# schematic-for-manuf.net
KiCad netlist of a schematic drawn in EAGLE
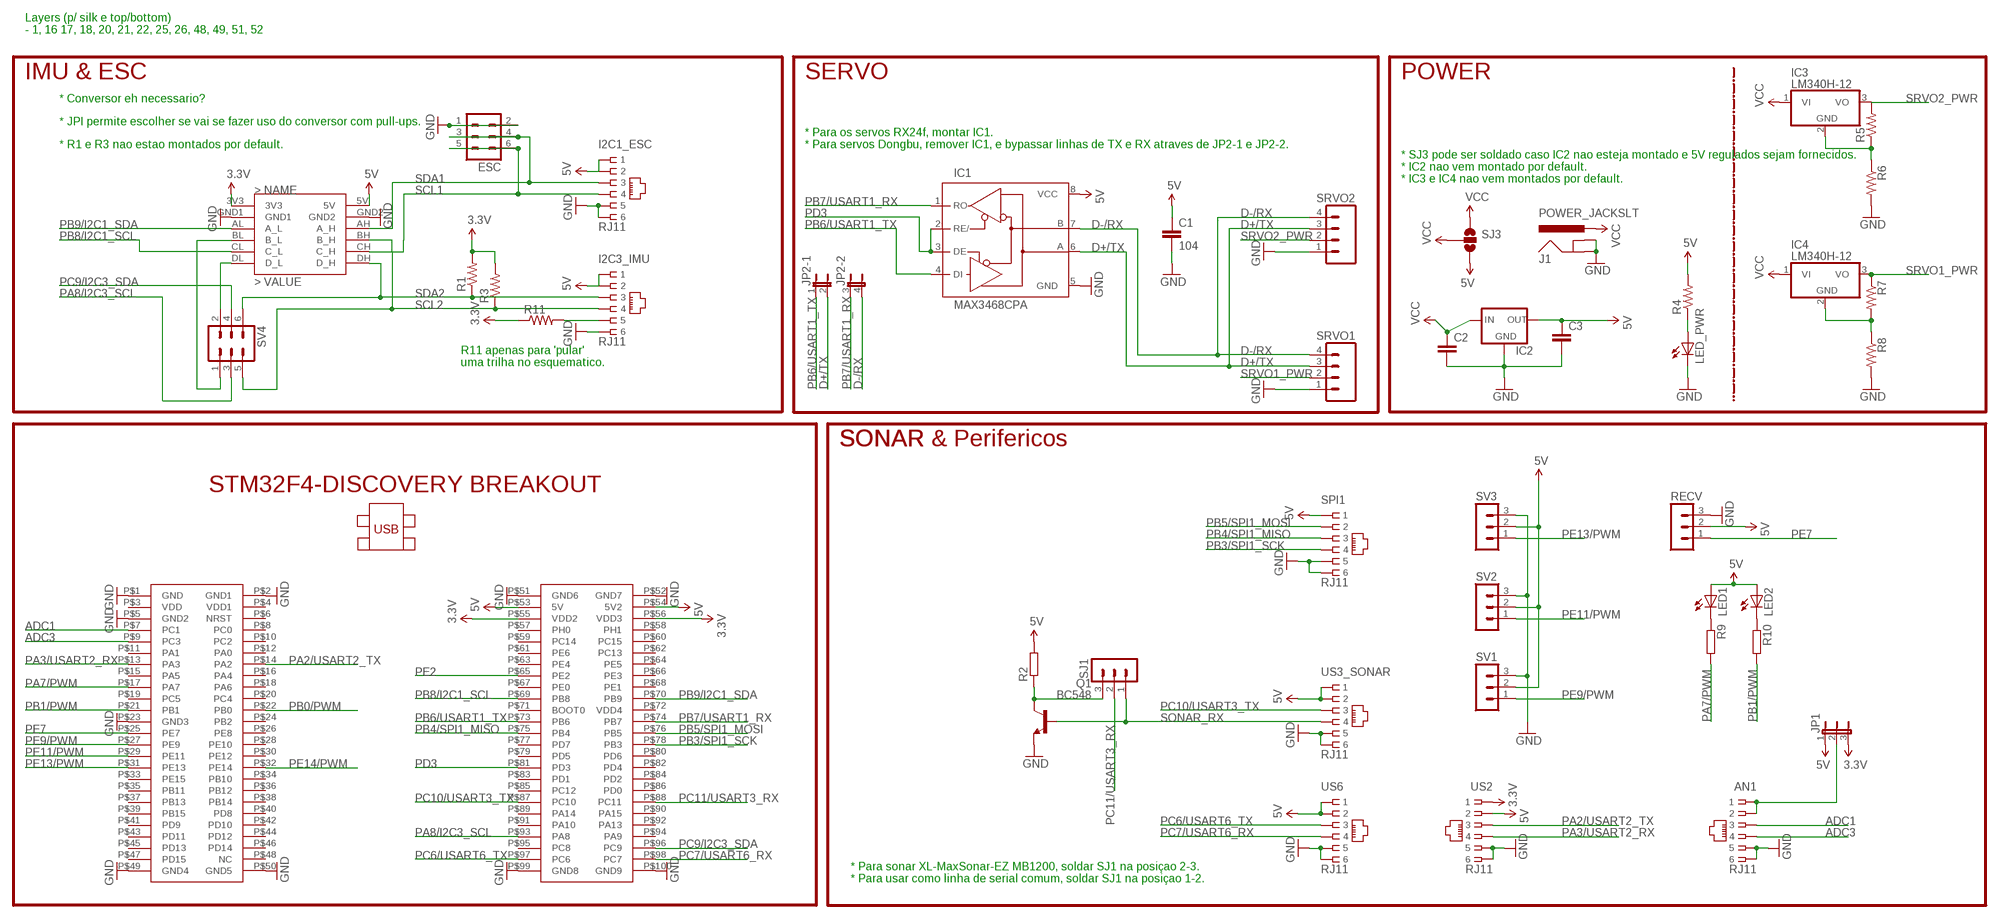
[diagram p0: schematic, sheet 1]

(export (version "E")
  (design (tool "Eeschema 10.0.6"))
  (components
    (comp (ref "AN1")
      (value "RJ11")
      (footprint "eagle-import:RJ12-PROVANT")
      (libsource (lib "eagle-import") (part "RJ11"))
    )
    (comp (ref "C1")
      (value "104")
      (footprint "eagle-import:CAP-PTH-SMALL-KIT")
      (libsource (lib "eagle-import") (part "0.1UF-50V-20%(PTH)KIT-EZ"))
    )
    (comp (ref "C2")
      (value "C7.5/3")
      (footprint "eagle-import:C7.5B3")
      (libsource (lib "eagle-import") (part "C7.5/3"))
    )
    (comp (ref "C3")
      (value "0.1UF-50V-20%(PTH)KIT-EZ")
      (footprint "eagle-import:CAP-PTH-SMALL-KIT")
      (libsource (lib "eagle-import") (part "0.1UF-50V-20%(PTH)KIT-EZ"))
    )
    (comp (ref "ESC")
      (value "MA03-2")
      (footprint "eagle-import:MA03-2")
      (libsource (lib "eagle-import") (part "MA03-2"))
    )
    (comp (ref "I2C1_ESC")
      (value "RJ11")
      (footprint "eagle-import:RJ12-PROVANT")
      (libsource (lib "eagle-import") (part "RJ11"))
    )
    (comp (ref "I2C3_IMU")
      (value "RJ11")
      (footprint "eagle-import:RJ12-PROVANT")
      (libsource (lib "eagle-import") (part "RJ11"))
    )
    (comp (ref "IC1")
      (value "MAX3468CPA")
      (footprint "eagle-import:DIL08")
      (libsource (lib "eagle-import") (part "MAX34PA68C"))
    )
    (comp (ref "IC2")
      (value "V_REG_78XX-TO-220")
      (footprint "eagle-import:TO-220-ALT")
      (libsource (lib "eagle-import") (part "V_REG_78XX-TO-220"))
    )
    (comp (ref "IC3")
      (value "LM340H-12")
      (footprint "eagle-import:TO220H")
      (libsource (lib "eagle-import") (part "LM340?-H12"))
    )
    (comp (ref "IC4")
      (value "LM340H-12")
      (footprint "eagle-import:TO220H")
      (libsource (lib "eagle-import") (part "LM340?-H12"))
    )
    (comp (ref "J1")
      (value "POWER_JACKSLT")
      (footprint "eagle-import:POWER_JACK_SLOT")
      (libsource (lib "eagle-import") (part "POWER_JACKSLT"))
    )
    (comp (ref "JP1")
      (value "JP2E")
      (footprint "eagle-import:JP2")
      (libsource (lib "eagle-import") (part "JP2E"))
    )
    (comp (ref "JP2")
      (value "JP2QE")
      (footprint "eagle-import:JP2Q")
      (libsource (lib "eagle-import") (part "JP2QE"))
    )
    (comp (ref "LED1")
      (value "LED3MM")
      (footprint "eagle-import:LED3MM")
      (libsource (lib "eagle-import") (part "LED3MM"))
    )
    (comp (ref "LED2")
      (value "LED3MM")
      (footprint "eagle-import:LED3MM")
      (libsource (lib "eagle-import") (part "LED3MM"))
    )
    (comp (ref "LED_PWR")
      (value "LED5MM")
      (footprint "eagle-import:LED5MM")
      (libsource (lib "eagle-import") (part "LED5MM"))
    )
    (comp (ref "Q1")
      (value "BC548")
      (footprint "eagle-import:TO92-EBC")
      (libsource (lib "eagle-import") (part "BC548"))
    )
    (comp (ref "R1")
      (value "R-US_0204/5")
      (footprint "eagle-import:0204_5")
      (libsource (lib "eagle-import") (part "R-US_0204/5"))
    )
    (comp (ref "R2")
      (value "R-EU_0204/7")
      (footprint "eagle-import:0204_7")
      (libsource (lib "eagle-import") (part "R-EU_0204/7"))
    )
    (comp (ref "R3")
      (value "R-US_0204/5")
      (footprint "eagle-import:0204_5")
      (libsource (lib "eagle-import") (part "R-US_0204/5"))
    )
    (comp (ref "R4")
      (value "R-US_0204/7")
      (footprint "eagle-import:0204_7")
      (libsource (lib "eagle-import") (part "R-US_0204/7"))
    )
    (comp (ref "R5")
      (value "R-US_0204/7")
      (footprint "eagle-import:0204_7")
      (libsource (lib "eagle-import") (part "R-US_0204/7"))
    )
    (comp (ref "R6")
      (value "R-US_0204/7")
      (footprint "eagle-import:0204_7")
      (libsource (lib "eagle-import") (part "R-US_0204/7"))
    )
    (comp (ref "R7")
      (value "R-US_0204/7")
      (footprint "eagle-import:0204_7")
      (libsource (lib "eagle-import") (part "R-US_0204/7"))
    )
    (comp (ref "R8")
      (value "R-US_0204/7")
      (footprint "eagle-import:0204_7")
      (libsource (lib "eagle-import") (part "R-US_0204/7"))
    )
    (comp (ref "R9")
      (value "R-EU_0204/2V")
      (footprint "eagle-import:0204V")
      (libsource (lib "eagle-import") (part "R-EU_0204/2V"))
    )
    (comp (ref "R10")
      (value "R-EU_0204/2V")
      (footprint "eagle-import:0204V")
      (libsource (lib "eagle-import") (part "R-EU_0204/2V"))
    )
    (comp (ref "R11")
      (value "R-US_M1406")
      (footprint "eagle-import:M1406")
      (libsource (lib "eagle-import") (part "R-US_M1406"))
    )
    (comp (ref "RECV")
      (value "MA03-1")
      (footprint "eagle-import:MA03-1")
      (libsource (lib "eagle-import") (part "MA03-1"))
    )
    (comp (ref "SJ1")
      (value "MA03-1")
      (footprint "eagle-import:MA03-1")
      (libsource (lib "eagle-import") (part "MA03-1"))
    )
    (comp (ref "SJ3")
      (value "SOLDERJUMPER_2WAY-OLDW")
      (footprint "eagle-import:SJ_2W")
      (libsource (lib "eagle-import") (part "SOLDERJUMPER_2WAY-OLDW"))
    )
    (comp (ref "SPI1")
      (value "RJ11")
      (footprint "eagle-import:RJ12-PROVANT")
      (libsource (lib "eagle-import") (part "RJ11"))
    )
    (comp (ref "SRVO1")
      (value "M04POLAR")
      (footprint "eagle-import:MOLEX-1X4")
      (libsource (lib "eagle-import") (part "M04POLAR"))
    )
    (comp (ref "SRVO2")
      (value "M04POLAR")
      (footprint "eagle-import:MOLEX-1X4")
      (libsource (lib "eagle-import") (part "M04POLAR"))
    )
    (comp (ref "SV1")
      (value "MA03-1")
      (footprint "eagle-import:MA03-1")
      (libsource (lib "eagle-import") (part "MA03-1"))
    )
    (comp (ref "SV2")
      (value "MA03-1")
      (footprint "eagle-import:MA03-1")
      (libsource (lib "eagle-import") (part "MA03-1"))
    )
    (comp (ref "SV3")
      (value "MA03-1")
      (footprint "eagle-import:MA03-1")
      (libsource (lib "eagle-import") (part "MA03-1"))
    )
    (comp (ref "SV4")
      (value "MA03-2")
      (footprint "eagle-import:MA03-2")
      (libsource (lib "eagle-import") (part "MA03-2"))
    )
    (comp (ref "U$1")
      (value "STM32F4-DISCOVERY")
      (footprint "eagle-import:STM32F4-DISCOVERY")
      (libsource (lib "eagle-import") (part "STM32F4-DISCOVERY"))
    )
    (comp (ref "U$2")
      (value "JYMCU_LOGIC_LEVEL_CONVERTER")
      (footprint "eagle-import:JYMCU_LOGIC_LEVEL_SHIFTER_DIP")
      (libsource (lib "eagle-import") (part "JYMCU_LOGIC_LEVEL_CONVERTER"))
    )
    (comp (ref "US2")
      (value "RJ11")
      (footprint "eagle-import:RJ12-PROVANT")
      (libsource (lib "eagle-import") (part "RJ11"))
    )
    (comp (ref "US3_SONAR")
      (value "RJ11")
      (footprint "eagle-import:RJ12-PROVANT")
      (libsource (lib "eagle-import") (part "RJ11"))
    )
    (comp (ref "US6")
      (value "RJ11")
      (footprint "eagle-import:RJ12-PROVANT")
      (libsource (lib "eagle-import") (part "RJ11"))
    )
  )
  (nets
    (net (code "1") (name "/ADC1") (class "Default")
      (node (ref "AN1") (pin "P3") (pinfunction "3_P3") (pintype "passive"))
      (node (ref "U$1") (pin "P$7") (pinfunction "PC1_P$7") (pintype "bidirectional"))
    )
    (net (code "2") (name "/ADC3") (class "Default")
      (node (ref "AN1") (pin "P4") (pinfunction "4_P4") (pintype "passive"))
      (node (ref "U$1") (pin "P$9") (pinfunction "PC3_P$9") (pintype "bidirectional"))
    )
    (net (code "3") (name "/D+{slash}TX") (class "Default")
      (node (ref "IC1") (pin "6") (pinfunction "A_6") (pintype "passive"))
      (node (ref "JP2") (pin "2") (pinfunction "2_2") (pintype "passive"))
      (node (ref "SRVO1") (pin "3") (pinfunction "3_3") (pintype "passive"))
      (node (ref "SRVO2") (pin "3") (pinfunction "3_3") (pintype "passive"))
    )
    (net (code "4") (name "/D-{slash}RX") (class "Default")
      (node (ref "IC1") (pin "7") (pinfunction "B_7") (pintype "passive"))
      (node (ref "JP2") (pin "4") (pinfunction "2_4") (pintype "passive"))
      (node (ref "SRVO1") (pin "4") (pinfunction "4_4") (pintype "passive"))
      (node (ref "SRVO2") (pin "4") (pinfunction "4_4") (pintype "passive"))
    )
    (net (code "5") (name "/PA2{slash}USART2_TX") (class "Default")
      (node (ref "U$1") (pin "P$14") (pinfunction "PA2_P$14") (pintype "bidirectional"))
      (node (ref "US2") (pin "P3") (pinfunction "3_P3") (pintype "passive"))
    )
    (net (code "6") (name "/PA3{slash}USART2_RX") (class "Default")
      (node (ref "U$1") (pin "P$13") (pinfunction "PA3_P$13") (pintype "bidirectional"))
      (node (ref "US2") (pin "P4") (pinfunction "4_P4") (pintype "passive"))
    )
    (net (code "7") (name "/PA7{slash}PWM") (class "Default")
      (node (ref "R9") (pin "2") (pinfunction "2_2") (pintype "passive"))
      (node (ref "U$1") (pin "P$17") (pinfunction "PA7_P$17") (pintype "bidirectional"))
    )
    (net (code "8") (name "/PA8{slash}I2C3_SCL") (class "Default")
      (node (ref "SV4") (pin "3") (pinfunction "3_3") (pintype "passive"))
      (node (ref "U$1") (pin "P$93") (pinfunction "PA8_P$93") (pintype "bidirectional"))
    )
    (net (code "9") (name "/PB0{slash}PWM") (class "Default")
      (node (ref "U$1") (pin "P$22") (pinfunction "PB0_P$22") (pintype "bidirectional"))
    )
    (net (code "10") (name "/PB1{slash}PWM") (class "Default")
      (node (ref "R10") (pin "2") (pinfunction "2_2") (pintype "passive"))
      (node (ref "U$1") (pin "P$21") (pinfunction "PB1_P$21") (pintype "bidirectional"))
    )
    (net (code "11") (name "/PB3{slash}SPI1_SCK") (class "Default")
      (node (ref "SPI1") (pin "P4") (pinfunction "4_P4") (pintype "passive"))
      (node (ref "U$1") (pin "P$78") (pinfunction "PB3_P$78") (pintype "bidirectional"))
    )
    (net (code "12") (name "/PB4{slash}SPI1_MISO") (class "Default")
      (node (ref "SPI1") (pin "P3") (pinfunction "3_P3") (pintype "passive"))
      (node (ref "U$1") (pin "P$75") (pinfunction "PB4_P$75") (pintype "bidirectional"))
    )
    (net (code "13") (name "/PB5{slash}SPI1_MOSI") (class "Default")
      (node (ref "SPI1") (pin "P2") (pinfunction "2_P2") (pintype "passive"))
      (node (ref "U$1") (pin "P$76") (pinfunction "PB5_P$76") (pintype "bidirectional"))
    )
    (net (code "14") (name "/PB6{slash}USART1_TX") (class "Default")
      (node (ref "IC1") (pin "4") (pinfunction "DI_4") (pintype "input"))
      (node (ref "JP2") (pin "1") (pinfunction "1_1") (pintype "passive"))
      (node (ref "U$1") (pin "P$73") (pinfunction "PB6_P$73") (pintype "bidirectional"))
    )
    (net (code "15") (name "/PB7{slash}USART1_RX") (class "Default")
      (node (ref "IC1") (pin "1") (pinfunction "RO_1") (pintype "output"))
      (node (ref "JP2") (pin "3") (pinfunction "1_3") (pintype "passive"))
      (node (ref "U$1") (pin "P$74") (pinfunction "PB7_P$74") (pintype "bidirectional"))
    )
    (net (code "16") (name "/PB8{slash}I2C1_SCL") (class "Default")
      (node (ref "U$1") (pin "P$69") (pinfunction "PB8_P$69") (pintype "bidirectional"))
      (node (ref "U$2") (pin "CL") (pinfunction "C_L_CL") (pintype "bidirectional"))
    )
    (net (code "17") (name "/PB9{slash}I2C1_SDA") (class "Default")
      (node (ref "U$1") (pin "P$70") (pinfunction "PB9_P$70") (pintype "bidirectional"))
      (node (ref "U$2") (pin "AL") (pinfunction "A_L_AL") (pintype "bidirectional"))
    )
    (net (code "18") (name "/PC6{slash}USART6_TX") (class "Default")
      (node (ref "U$1") (pin "P$97") (pinfunction "PC6_P$97") (pintype "bidirectional"))
      (node (ref "US6") (pin "P3") (pinfunction "3_P3") (pintype "passive"))
    )
    (net (code "19") (name "/PC7{slash}USART6_RX") (class "Default")
      (node (ref "U$1") (pin "P$98") (pinfunction "PC7_P$98") (pintype "bidirectional"))
      (node (ref "US6") (pin "P4") (pinfunction "4_P4") (pintype "passive"))
    )
    (net (code "20") (name "/PC9{slash}I2C3_SDA") (class "Default")
      (node (ref "SV4") (pin "4") (pinfunction "4_4") (pintype "passive"))
      (node (ref "U$1") (pin "P$96") (pinfunction "PC9_P$96") (pintype "bidirectional"))
    )
    (net (code "21") (name "/PC10{slash}USART3_TX") (class "Default")
      (node (ref "U$1") (pin "P$87") (pinfunction "PC10_P$87") (pintype "bidirectional"))
      (node (ref "US3_SONAR") (pin "P3") (pinfunction "3_P3") (pintype "passive"))
    )
    (net (code "22") (name "/PC11{slash}USART3_RX") (class "Default")
      (node (ref "SJ1") (pin "2") (pinfunction "2_2") (pintype "passive"))
      (node (ref "U$1") (pin "P$88") (pinfunction "PC11_P$88") (pintype "bidirectional"))
    )
    (net (code "23") (name "/PD3") (class "Default")
      (node (ref "IC1") (pin "2") (pinfunction "RE/_2") (pintype "input"))
      (node (ref "IC1") (pin "3") (pinfunction "DE_3") (pintype "input"))
      (node (ref "U$1") (pin "P$81") (pinfunction "PD3_P$81") (pintype "bidirectional"))
    )
    (net (code "24") (name "/PE2") (class "Default")
      (node (ref "U$1") (pin "P$65") (pinfunction "PE2_P$65") (pintype "bidirectional"))
    )
    (net (code "25") (name "/PE7") (class "Default")
      (node (ref "RECV") (pin "1") (pinfunction "1_1") (pintype "passive"))
      (node (ref "U$1") (pin "P$25") (pinfunction "PE7_P$25") (pintype "bidirectional"))
    )
    (net (code "26") (name "/PE9{slash}PWM") (class "Default")
      (node (ref "SV1") (pin "1") (pinfunction "1_1") (pintype "passive"))
      (node (ref "U$1") (pin "P$27") (pinfunction "PE9_P$27") (pintype "bidirectional"))
    )
    (net (code "27") (name "/PE11{slash}PWM") (class "Default")
      (node (ref "SV2") (pin "1") (pinfunction "1_1") (pintype "passive"))
      (node (ref "U$1") (pin "P$29") (pinfunction "PE11_P$29") (pintype "bidirectional"))
    )
    (net (code "28") (name "/PE13{slash}PWM") (class "Default")
      (node (ref "SV3") (pin "1") (pinfunction "1_1") (pintype "passive"))
      (node (ref "U$1") (pin "P$31") (pinfunction "PE13_P$31") (pintype "bidirectional"))
    )
    (net (code "29") (name "/PE14{slash}PWM") (class "Default")
      (node (ref "U$1") (pin "P$32") (pinfunction "PE14_P$32") (pintype "bidirectional"))
    )
    (net (code "30") (name "/SCL1") (class "Default")
      (node (ref "ESC") (pin "5") (pinfunction "5_5") (pintype "passive"))
      (node (ref "ESC") (pin "6") (pinfunction "6_6") (pintype "passive"))
      (node (ref "I2C1_ESC") (pin "P4") (pinfunction "4_P4") (pintype "passive"))
      (node (ref "U$2") (pin "CH") (pinfunction "C_H_CH") (pintype "bidirectional"))
    )
    (net (code "31") (name "/SCL2") (class "Default")
      (node (ref "I2C3_IMU") (pin "P4") (pinfunction "4_P4") (pintype "passive"))
      (node (ref "R3") (pin "1") (pinfunction "1_1") (pintype "passive"))
      (node (ref "SV4") (pin "5") (pinfunction "5_5") (pintype "passive"))
      (node (ref "U$2") (pin "BH") (pinfunction "B_H_BH") (pintype "bidirectional"))
    )
    (net (code "32") (name "/SDA1") (class "Default")
      (node (ref "ESC") (pin "3") (pinfunction "3_3") (pintype "passive"))
      (node (ref "ESC") (pin "4") (pinfunction "4_4") (pintype "passive"))
      (node (ref "I2C1_ESC") (pin "P3") (pinfunction "3_P3") (pintype "passive"))
      (node (ref "U$2") (pin "AH") (pinfunction "A_H_AH") (pintype "bidirectional"))
    )
    (net (code "33") (name "/SDA2") (class "Default")
      (node (ref "I2C3_IMU") (pin "P3") (pinfunction "3_P3") (pintype "passive"))
      (node (ref "R1") (pin "1") (pinfunction "1_1") (pintype "passive"))
      (node (ref "SV4") (pin "6") (pinfunction "6_6") (pintype "passive"))
      (node (ref "U$2") (pin "DH") (pinfunction "D_H_DH") (pintype "bidirectional"))
    )
    (net (code "34") (name "/SONAR_RX") (class "Default")
      (node (ref "Q1") (pin "B") (pinfunction "B_B") (pintype "passive"))
      (node (ref "SJ1") (pin "1") (pinfunction "1_1") (pintype "passive"))
      (node (ref "US3_SONAR") (pin "P4") (pinfunction "4_P4") (pintype "passive"))
    )
    (net (code "35") (name "/SRVO1_PWR") (class "Default")
      (node (ref "IC4") (pin "3") (pinfunction "VO_3") (pintype "passive"))
      (node (ref "R7") (pin "1") (pinfunction "1_1") (pintype "passive"))
      (node (ref "SRVO1") (pin "2") (pinfunction "2_2") (pintype "passive"))
    )
    (net (code "36") (name "/SRVO2_PWR") (class "Default")
      (node (ref "IC3") (pin "3") (pinfunction "VO_3") (pintype "passive"))
      (node (ref "R5") (pin "2") (pinfunction "2_2") (pintype "passive"))
      (node (ref "SRVO2") (pin "2") (pinfunction "2_2") (pintype "passive"))
    )
    (net (code "37") (name "3.3V") (class "Default")
      (node (ref "JP1") (pin "3") (pinfunction "3_3") (pintype "passive"))
      (node (ref "R1") (pin "2") (pinfunction "2_2") (pintype "passive"))
      (node (ref "R11") (pin "1") (pinfunction "1_1") (pintype "passive"))
      (node (ref "R3") (pin "2") (pinfunction "2_2") (pintype "passive"))
      (node (ref "U$1") (pin "P$55") (pinfunction "VDD2_P$55") (pintype "bidirectional"))
      (node (ref "U$1") (pin "P$56") (pinfunction "VDD3_P$56") (pintype "bidirectional"))
      (node (ref "U$2") (pin "3V3") (pinfunction "3V3_3V3") (pintype "bidirectional"))
      (node (ref "US2") (pin "P1") (pinfunction "1_P1") (pintype "passive"))
    )
    (net (code "38") (name "5V") (class "Default")
      (node (ref "C1") (pin "1") (pinfunction "1_1") (pintype "passive"))
      (node (ref "C3") (pin "1") (pinfunction "1_1") (pintype "passive"))
      (node (ref "I2C1_ESC") (pin "P1") (pinfunction "1_P1") (pintype "passive"))
      (node (ref "I2C1_ESC") (pin "P2") (pinfunction "2_P2") (pintype "passive"))
      (node (ref "I2C3_IMU") (pin "P1") (pinfunction "1_P1") (pintype "passive"))
      (node (ref "I2C3_IMU") (pin "P2") (pinfunction "2_P2") (pintype "passive"))
      (node (ref "IC1") (pin "8") (pinfunction "VCC_8") (pintype "power_in"))
      (node (ref "IC2") (pin "OUT") (pinfunction "OUT_OUT") (pintype "output"))
      (node (ref "JP1") (pin "1") (pinfunction "1_1") (pintype "passive"))
      (node (ref "LED1") (pin "A") (pinfunction "A_A") (pintype "passive"))
      (node (ref "LED2") (pin "A") (pinfunction "A_A") (pintype "passive"))
      (node (ref "R2") (pin "2") (pinfunction "2_2") (pintype "passive"))
      (node (ref "R4") (pin "2") (pinfunction "2_2") (pintype "passive"))
      (node (ref "RECV") (pin "2") (pinfunction "2_2") (pintype "passive"))
      (node (ref "SJ3") (pin "3") (pinfunction "3_3") (pintype "passive"))
      (node (ref "SPI1") (pin "P1") (pinfunction "1_P1") (pintype "passive"))
      (node (ref "SV1") (pin "2") (pinfunction "2_2") (pintype "passive"))
      (node (ref "SV2") (pin "2") (pinfunction "2_2") (pintype "passive"))
      (node (ref "SV3") (pin "2") (pinfunction "2_2") (pintype "passive"))
      (node (ref "U$1") (pin "P$53") (pinfunction "5V_P$53") (pintype "bidirectional"))
      (node (ref "U$1") (pin "P$54") (pinfunction "5V2_P$54") (pintype "bidirectional"))
      (node (ref "U$2") (pin "5V") (pinfunction "5V_5V") (pintype "bidirectional"))
      (node (ref "US2") (pin "P2") (pinfunction "2_P2") (pintype "passive"))
      (node (ref "US3_SONAR") (pin "P1") (pinfunction "1_P1") (pintype "passive"))
      (node (ref "US3_SONAR") (pin "P2") (pinfunction "2_P2") (pintype "passive"))
      (node (ref "US6") (pin "P1") (pinfunction "1_P1") (pintype "passive"))
      (node (ref "US6") (pin "P2") (pinfunction "2_P2") (pintype "passive"))
    )
    (net (code "39") (name "GND") (class "Default")
      (node (ref "AN1") (pin "P5") (pinfunction "5_P5") (pintype "passive"))
      (node (ref "AN1") (pin "P6") (pinfunction "6_P6") (pintype "passive"))
      (node (ref "C1") (pin "2") (pinfunction "2_2") (pintype "passive"))
      (node (ref "C2") (pin "2") (pinfunction "2_2") (pintype "passive"))
      (node (ref "C3") (pin "2") (pinfunction "2_2") (pintype "passive"))
      (node (ref "ESC") (pin "1") (pinfunction "1_1") (pintype "passive"))
      (node (ref "ESC") (pin "2") (pinfunction "2_2") (pintype "passive"))
      (node (ref "I2C1_ESC") (pin "P5") (pinfunction "5_P5") (pintype "passive"))
      (node (ref "I2C1_ESC") (pin "P6") (pinfunction "6_P6") (pintype "passive"))
      (node (ref "I2C3_IMU") (pin "P6") (pinfunction "6_P6") (pintype "passive"))
      (node (ref "IC1") (pin "5") (pinfunction "GND_5") (pintype "power_in"))
      (node (ref "IC2") (pin "GND") (pinfunction "GND_GND") (pintype "input"))
      (node (ref "J1") (pin "GND@1") (pinfunction "GNDBREAK_GND@1") (pintype "bidirectional"))
      (node (ref "J1") (pin "GND@2") (pinfunction "GND_GND@2") (pintype "bidirectional"))
      (node (ref "LED_PWR") (pin "K") (pinfunction "C_K") (pintype "passive"))
      (node (ref "Q1") (pin "E") (pinfunction "E_E") (pintype "passive"))
      (node (ref "R6") (pin "2") (pinfunction "2_2") (pintype "passive"))
      (node (ref "R8") (pin "2") (pinfunction "2_2") (pintype "passive"))
      (node (ref "RECV") (pin "3") (pinfunction "3_3") (pintype "passive"))
      (node (ref "SPI1") (pin "P5") (pinfunction "5_P5") (pintype "passive"))
      (node (ref "SPI1") (pin "P6") (pinfunction "6_P6") (pintype "passive"))
      (node (ref "SRVO1") (pin "1") (pinfunction "1_1") (pintype "passive"))
      (node (ref "SRVO2") (pin "1") (pinfunction "1_1") (pintype "passive"))
      (node (ref "SV1") (pin "3") (pinfunction "3_3") (pintype "passive"))
      (node (ref "SV2") (pin "3") (pinfunction "3_3") (pintype "passive"))
      (node (ref "SV3") (pin "3") (pinfunction "3_3") (pintype "passive"))
      (node (ref "U$1") (pin "P$1") (pinfunction "GND_P$1") (pintype "bidirectional"))
      (node (ref "U$1") (pin "P$100") (pinfunction "GND9_P$100") (pintype "bidirectional"))
      (node (ref "U$1") (pin "P$2") (pinfunction "GND1_P$2") (pintype "bidirectional"))
      (node (ref "U$1") (pin "P$23") (pinfunction "GND3_P$23") (pintype "bidirectional"))
      (node (ref "U$1") (pin "P$49") (pinfunction "GND4_P$49") (pintype "bidirectional"))
      (node (ref "U$1") (pin "P$5") (pinfunction "GND2_P$5") (pintype "bidirectional"))
      (node (ref "U$1") (pin "P$50") (pinfunction "GND5_P$50") (pintype "bidirectional"))
      (node (ref "U$1") (pin "P$51") (pinfunction "GND6_P$51") (pintype "bidirectional"))
      (node (ref "U$1") (pin "P$52") (pinfunction "GND7_P$52") (pintype "bidirectional"))
      (node (ref "U$1") (pin "P$99") (pinfunction "GND8_P$99") (pintype "bidirectional"))
      (node (ref "U$2") (pin "GND1") (pinfunction "GND1_GND1") (pintype "bidirectional"))
      (node (ref "U$2") (pin "GND2") (pinfunction "GND2_GND2") (pintype "bidirectional"))
      (node (ref "US2") (pin "P5") (pinfunction "5_P5") (pintype "passive"))
      (node (ref "US2") (pin "P6") (pinfunction "6_P6") (pintype "passive"))
      (node (ref "US3_SONAR") (pin "P5") (pinfunction "5_P5") (pintype "passive"))
      (node (ref "US3_SONAR") (pin "P6") (pinfunction "6_P6") (pintype "passive"))
      (node (ref "US6") (pin "P5") (pinfunction "5_P5") (pintype "passive"))
      (node (ref "US6") (pin "P6") (pinfunction "6_P6") (pintype "passive"))
    )
    (net (code "40") (name "Net-(AN1-1)") (class "Default")
      (node (ref "AN1") (pin "P1") (pinfunction "1_P1") (pintype "passive"))
      (node (ref "AN1") (pin "P2") (pinfunction "2_P2") (pintype "passive"))
      (node (ref "JP1") (pin "2") (pinfunction "2_2") (pintype "passive"))
    )
    (net (code "41") (name "Net-(I2C3_IMU-5)") (class "Default")
      (node (ref "I2C3_IMU") (pin "P5") (pinfunction "5_P5") (pintype "passive"))
      (node (ref "R11") (pin "2") (pinfunction "2_2") (pintype "passive"))
    )
    (net (code "42") (name "Net-(IC3-GND)") (class "Default")
      (node (ref "IC3") (pin "2") (pinfunction "GND_2") (pintype "passive"))
      (node (ref "R5") (pin "1") (pinfunction "1_1") (pintype "passive"))
      (node (ref "R6") (pin "1") (pinfunction "1_1") (pintype "passive"))
    )
    (net (code "43") (name "Net-(IC4-GND)") (class "Default")
      (node (ref "IC4") (pin "2") (pinfunction "GND_2") (pintype "passive"))
      (node (ref "R7") (pin "2") (pinfunction "2_2") (pintype "passive"))
      (node (ref "R8") (pin "1") (pinfunction "1_1") (pintype "passive"))
    )
    (net (code "44") (name "Net-(LED1-C)") (class "Default")
      (node (ref "LED1") (pin "K") (pinfunction "C_K") (pintype "passive"))
      (node (ref "R9") (pin "1") (pinfunction "1_1") (pintype "passive"))
    )
    (net (code "45") (name "Net-(LED2-C)") (class "Default")
      (node (ref "LED2") (pin "K") (pinfunction "C_K") (pintype "passive"))
      (node (ref "R10") (pin "1") (pinfunction "1_1") (pintype "passive"))
    )
    (net (code "46") (name "Net-(LED_PWR-PadA)") (class "Default")
      (node (ref "LED_PWR") (pin "A") (pinfunction "A_A") (pintype "passive"))
      (node (ref "R4") (pin "1") (pinfunction "1_1") (pintype "passive"))
    )
    (net (code "47") (name "Net-(Q1-PadC)") (class "Default")
      (node (ref "Q1") (pin "C") (pinfunction "C_C") (pintype "passive"))
      (node (ref "R2") (pin "1") (pinfunction "1_1") (pintype "passive"))
      (node (ref "SJ1") (pin "3") (pinfunction "3_3") (pintype "passive"))
    )
    (net (code "48") (name "Net-(U$2-B_L)") (class "Default")
      (node (ref "SV4") (pin "1") (pinfunction "1_1") (pintype "passive"))
      (node (ref "U$2") (pin "BL") (pinfunction "B_L_BL") (pintype "bidirectional"))
    )
    (net (code "49") (name "Net-(U$2-D_L)") (class "Default")
      (node (ref "SV4") (pin "2") (pinfunction "2_2") (pintype "passive"))
      (node (ref "U$2") (pin "DL") (pinfunction "D_L_DL") (pintype "bidirectional"))
    )
    (net (code "50") (name "VCC") (class "Default")
      (node (ref "C2") (pin "1") (pinfunction "1_1") (pintype "passive"))
      (node (ref "IC2") (pin "IN") (pinfunction "IN_IN") (pintype "input"))
      (node (ref "IC3") (pin "1") (pinfunction "VI_1") (pintype "input"))
      (node (ref "IC4") (pin "1") (pinfunction "VI_1") (pintype "input"))
      (node (ref "J1") (pin "PWR") (pinfunction "PWR_PWR") (pintype "bidirectional"))
      (node (ref "SJ3") (pin "1") (pinfunction "1_1") (pintype "passive"))
      (node (ref "SJ3") (pin "2") (pinfunction "2_2") (pintype "passive"))
    )
    (net (code "51") (name "unconnected-(U$1-BOOT0-PadP$71)") (class "Default")
      (node (ref "U$1") (pin "P$71") (pinfunction "BOOT0_P$71") (pintype "bidirectional"))
    )
    (net (code "52") (name "unconnected-(U$1-NC-PadP$48)") (class "Default")
      (node (ref "U$1") (pin "P$48") (pinfunction "NC_P$48") (pintype "bidirectional"))
    )
    (net (code "53") (name "unconnected-(U$1-NRST-PadP$6)") (class "Default")
      (node (ref "U$1") (pin "P$6") (pinfunction "NRST_P$6") (pintype "bidirectional"))
    )
    (net (code "54") (name "unconnected-(U$1-PA0-PadP$12)") (class "Default")
      (node (ref "U$1") (pin "P$12") (pinfunction "PA0_P$12") (pintype "bidirectional"))
    )
    (net (code "55") (name "unconnected-(U$1-PA1-PadP$11)") (class "Default")
      (node (ref "U$1") (pin "P$11") (pinfunction "PA1_P$11") (pintype "bidirectional"))
    )
    (net (code "56") (name "unconnected-(U$1-PA4-PadP$16)") (class "Default")
      (node (ref "U$1") (pin "P$16") (pinfunction "PA4_P$16") (pintype "bidirectional"))
    )
    (net (code "57") (name "unconnected-(U$1-PA5-PadP$15)") (class "Default")
      (node (ref "U$1") (pin "P$15") (pinfunction "PA5_P$15") (pintype "bidirectional"))
    )
    (net (code "58") (name "unconnected-(U$1-PA6-PadP$18)") (class "Default")
      (node (ref "U$1") (pin "P$18") (pinfunction "PA6_P$18") (pintype "bidirectional"))
    )
    (net (code "59") (name "unconnected-(U$1-PA9-PadP$94)") (class "Default")
      (node (ref "U$1") (pin "P$94") (pinfunction "PA9_P$94") (pintype "bidirectional"))
    )
    (net (code "60") (name "unconnected-(U$1-PA10-PadP$91)") (class "Default")
      (node (ref "U$1") (pin "P$91") (pinfunction "PA10_P$91") (pintype "bidirectional"))
    )
    (net (code "61") (name "unconnected-(U$1-PA13-PadP$92)") (class "Default")
      (node (ref "U$1") (pin "P$92") (pinfunction "PA13_P$92") (pintype "bidirectional"))
    )
    (net (code "62") (name "unconnected-(U$1-PA14-PadP$89)") (class "Default")
      (node (ref "U$1") (pin "P$89") (pinfunction "PA14_P$89") (pintype "bidirectional"))
    )
    (net (code "63") (name "unconnected-(U$1-PA15-PadP$90)") (class "Default")
      (node (ref "U$1") (pin "P$90") (pinfunction "PA15_P$90") (pintype "bidirectional"))
    )
    (net (code "64") (name "unconnected-(U$1-PB2-PadP$24)") (class "Default")
      (node (ref "U$1") (pin "P$24") (pinfunction "PB2_P$24") (pintype "bidirectional"))
    )
    (net (code "65") (name "unconnected-(U$1-PB10-PadP$34)") (class "Default")
      (node (ref "U$1") (pin "P$34") (pinfunction "PB10_P$34") (pintype "bidirectional"))
    )
    (net (code "66") (name "unconnected-(U$1-PB11-PadP$35)") (class "Default")
      (node (ref "U$1") (pin "P$35") (pinfunction "PB11_P$35") (pintype "bidirectional"))
    )
    (net (code "67") (name "unconnected-(U$1-PB12-PadP$36)") (class "Default")
      (node (ref "U$1") (pin "P$36") (pinfunction "PB12_P$36") (pintype "bidirectional"))
    )
    (net (code "68") (name "unconnected-(U$1-PB13-PadP$37)") (class "Default")
      (node (ref "U$1") (pin "P$37") (pinfunction "PB13_P$37") (pintype "bidirectional"))
    )
    (net (code "69") (name "unconnected-(U$1-PB14-PadP$38)") (class "Default")
      (node (ref "U$1") (pin "P$38") (pinfunction "PB14_P$38") (pintype "bidirectional"))
    )
    (net (code "70") (name "unconnected-(U$1-PB15-PadP$39)") (class "Default")
      (node (ref "U$1") (pin "P$39") (pinfunction "PB15_P$39") (pintype "bidirectional"))
    )
    (net (code "71") (name "unconnected-(U$1-PC0-PadP$8)") (class "Default")
      (node (ref "U$1") (pin "P$8") (pinfunction "PC0_P$8") (pintype "bidirectional"))
    )
    (net (code "72") (name "unconnected-(U$1-PC2-PadP$10)") (class "Default")
      (node (ref "U$1") (pin "P$10") (pinfunction "PC2_P$10") (pintype "bidirectional"))
    )
    (net (code "73") (name "unconnected-(U$1-PC4-PadP$20)") (class "Default")
      (node (ref "U$1") (pin "P$20") (pinfunction "PC4_P$20") (pintype "bidirectional"))
    )
    (net (code "74") (name "unconnected-(U$1-PC5-PadP$19)") (class "Default")
      (node (ref "U$1") (pin "P$19") (pinfunction "PC5_P$19") (pintype "bidirectional"))
    )
    (net (code "75") (name "unconnected-(U$1-PC8-PadP$95)") (class "Default")
      (node (ref "U$1") (pin "P$95") (pinfunction "PC8_P$95") (pintype "bidirectional"))
    )
    (net (code "76") (name "unconnected-(U$1-PC12-PadP$85)") (class "Default")
      (node (ref "U$1") (pin "P$85") (pinfunction "PC12_P$85") (pintype "bidirectional"))
    )
    (net (code "77") (name "unconnected-(U$1-PC13-PadP$62)") (class "Default")
      (node (ref "U$1") (pin "P$62") (pinfunction "PC13_P$62") (pintype "bidirectional"))
    )
    (net (code "78") (name "unconnected-(U$1-PC14-PadP$59)") (class "Default")
      (node (ref "U$1") (pin "P$59") (pinfunction "PC14_P$59") (pintype "bidirectional"))
    )
    (net (code "79") (name "unconnected-(U$1-PC15-PadP$60)") (class "Default")
      (node (ref "U$1") (pin "P$60") (pinfunction "PC15_P$60") (pintype "bidirectional"))
    )
    (net (code "80") (name "unconnected-(U$1-PD0-PadP$86)") (class "Default")
      (node (ref "U$1") (pin "P$86") (pinfunction "PD0_P$86") (pintype "bidirectional"))
    )
    (net (code "81") (name "unconnected-(U$1-PD1-PadP$83)") (class "Default")
      (node (ref "U$1") (pin "P$83") (pinfunction "PD1_P$83") (pintype "bidirectional"))
    )
    (net (code "82") (name "unconnected-(U$1-PD2-PadP$84)") (class "Default")
      (node (ref "U$1") (pin "P$84") (pinfunction "PD2_P$84") (pintype "bidirectional"))
    )
    (net (code "83") (name "unconnected-(U$1-PD4-PadP$82)") (class "Default")
      (node (ref "U$1") (pin "P$82") (pinfunction "PD4_P$82") (pintype "bidirectional"))
    )
    (net (code "84") (name "unconnected-(U$1-PD5-PadP$79)") (class "Default")
      (node (ref "U$1") (pin "P$79") (pinfunction "PD5_P$79") (pintype "bidirectional"))
    )
    (net (code "85") (name "unconnected-(U$1-PD6-PadP$80)") (class "Default")
      (node (ref "U$1") (pin "P$80") (pinfunction "PD6_P$80") (pintype "bidirectional"))
    )
    (net (code "86") (name "unconnected-(U$1-PD7-PadP$77)") (class "Default")
      (node (ref "U$1") (pin "P$77") (pinfunction "PD7_P$77") (pintype "bidirectional"))
    )
    (net (code "87") (name "unconnected-(U$1-PD8-PadP$40)") (class "Default")
      (node (ref "U$1") (pin "P$40") (pinfunction "PD8_P$40") (pintype "bidirectional"))
    )
    (net (code "88") (name "unconnected-(U$1-PD9-PadP$41)") (class "Default")
      (node (ref "U$1") (pin "P$41") (pinfunction "PD9_P$41") (pintype "bidirectional"))
    )
    (net (code "89") (name "unconnected-(U$1-PD10-PadP$42)") (class "Default")
      (node (ref "U$1") (pin "P$42") (pinfunction "PD10_P$42") (pintype "bidirectional"))
    )
    (net (code "90") (name "unconnected-(U$1-PD11-PadP$43)") (class "Default")
      (node (ref "U$1") (pin "P$43") (pinfunction "PD11_P$43") (pintype "bidirectional"))
    )
    (net (code "91") (name "unconnected-(U$1-PD12-PadP$44)") (class "Default")
      (node (ref "U$1") (pin "P$44") (pinfunction "PD12_P$44") (pintype "bidirectional"))
    )
    (net (code "92") (name "unconnected-(U$1-PD13-PadP$45)") (class "Default")
      (node (ref "U$1") (pin "P$45") (pinfunction "PD13_P$45") (pintype "bidirectional"))
    )
    (net (code "93") (name "unconnected-(U$1-PD14-PadP$46)") (class "Default")
      (node (ref "U$1") (pin "P$46") (pinfunction "PD14_P$46") (pintype "bidirectional"))
    )
    (net (code "94") (name "unconnected-(U$1-PD15-PadP$47)") (class "Default")
      (node (ref "U$1") (pin "P$47") (pinfunction "PD15_P$47") (pintype "bidirectional"))
    )
    (net (code "95") (name "unconnected-(U$1-PE0-PadP$67)") (class "Default")
      (node (ref "U$1") (pin "P$67") (pinfunction "PE0_P$67") (pintype "bidirectional"))
    )
    (net (code "96") (name "unconnected-(U$1-PE1-PadP$68)") (class "Default")
      (node (ref "U$1") (pin "P$68") (pinfunction "PE1_P$68") (pintype "bidirectional"))
    )
    (net (code "97") (name "unconnected-(U$1-PE3-PadP$66)") (class "Default")
      (node (ref "U$1") (pin "P$66") (pinfunction "PE3_P$66") (pintype "bidirectional"))
    )
    (net (code "98") (name "unconnected-(U$1-PE4-PadP$63)") (class "Default")
      (node (ref "U$1") (pin "P$63") (pinfunction "PE4_P$63") (pintype "bidirectional"))
    )
    (net (code "99") (name "unconnected-(U$1-PE5-PadP$64)") (class "Default")
      (node (ref "U$1") (pin "P$64") (pinfunction "PE5_P$64") (pintype "bidirectional"))
    )
    (net (code "100") (name "unconnected-(U$1-PE6-PadP$61)") (class "Default")
      (node (ref "U$1") (pin "P$61") (pinfunction "PE6_P$61") (pintype "bidirectional"))
    )
    (net (code "101") (name "unconnected-(U$1-PE8-PadP$26)") (class "Default")
      (node (ref "U$1") (pin "P$26") (pinfunction "PE8_P$26") (pintype "bidirectional"))
    )
    (net (code "102") (name "unconnected-(U$1-PE10-PadP$28)") (class "Default")
      (node (ref "U$1") (pin "P$28") (pinfunction "PE10_P$28") (pintype "bidirectional"))
    )
    (net (code "103") (name "unconnected-(U$1-PE12-PadP$30)") (class "Default")
      (node (ref "U$1") (pin "P$30") (pinfunction "PE12_P$30") (pintype "bidirectional"))
    )
    (net (code "104") (name "unconnected-(U$1-PE15-PadP$33)") (class "Default")
      (node (ref "U$1") (pin "P$33") (pinfunction "PE15_P$33") (pintype "bidirectional"))
    )
    (net (code "105") (name "unconnected-(U$1-PH0-PadP$57)") (class "Default")
      (node (ref "U$1") (pin "P$57") (pinfunction "PH0_P$57") (pintype "bidirectional"))
    )
    (net (code "106") (name "unconnected-(U$1-PH1-PadP$58)") (class "Default")
      (node (ref "U$1") (pin "P$58") (pinfunction "PH1_P$58") (pintype "bidirectional"))
    )
    (net (code "107") (name "unconnected-(U$1-VDD-PadP$3)") (class "Default")
      (node (ref "U$1") (pin "P$3") (pinfunction "VDD_P$3") (pintype "bidirectional"))
    )
    (net (code "108") (name "unconnected-(U$1-VDD1-PadP$4)") (class "Default")
      (node (ref "U$1") (pin "P$4") (pinfunction "VDD1_P$4") (pintype "bidirectional"))
    )
    (net (code "109") (name "unconnected-(U$1-VDD4-PadP$72)") (class "Default")
      (node (ref "U$1") (pin "P$72") (pinfunction "VDD4_P$72") (pintype "bidirectional"))
    )
  )
)
